# SHIFT_REGISTER_IC_74595.net
KiCad netlist of a schematic drawn in EAGLE
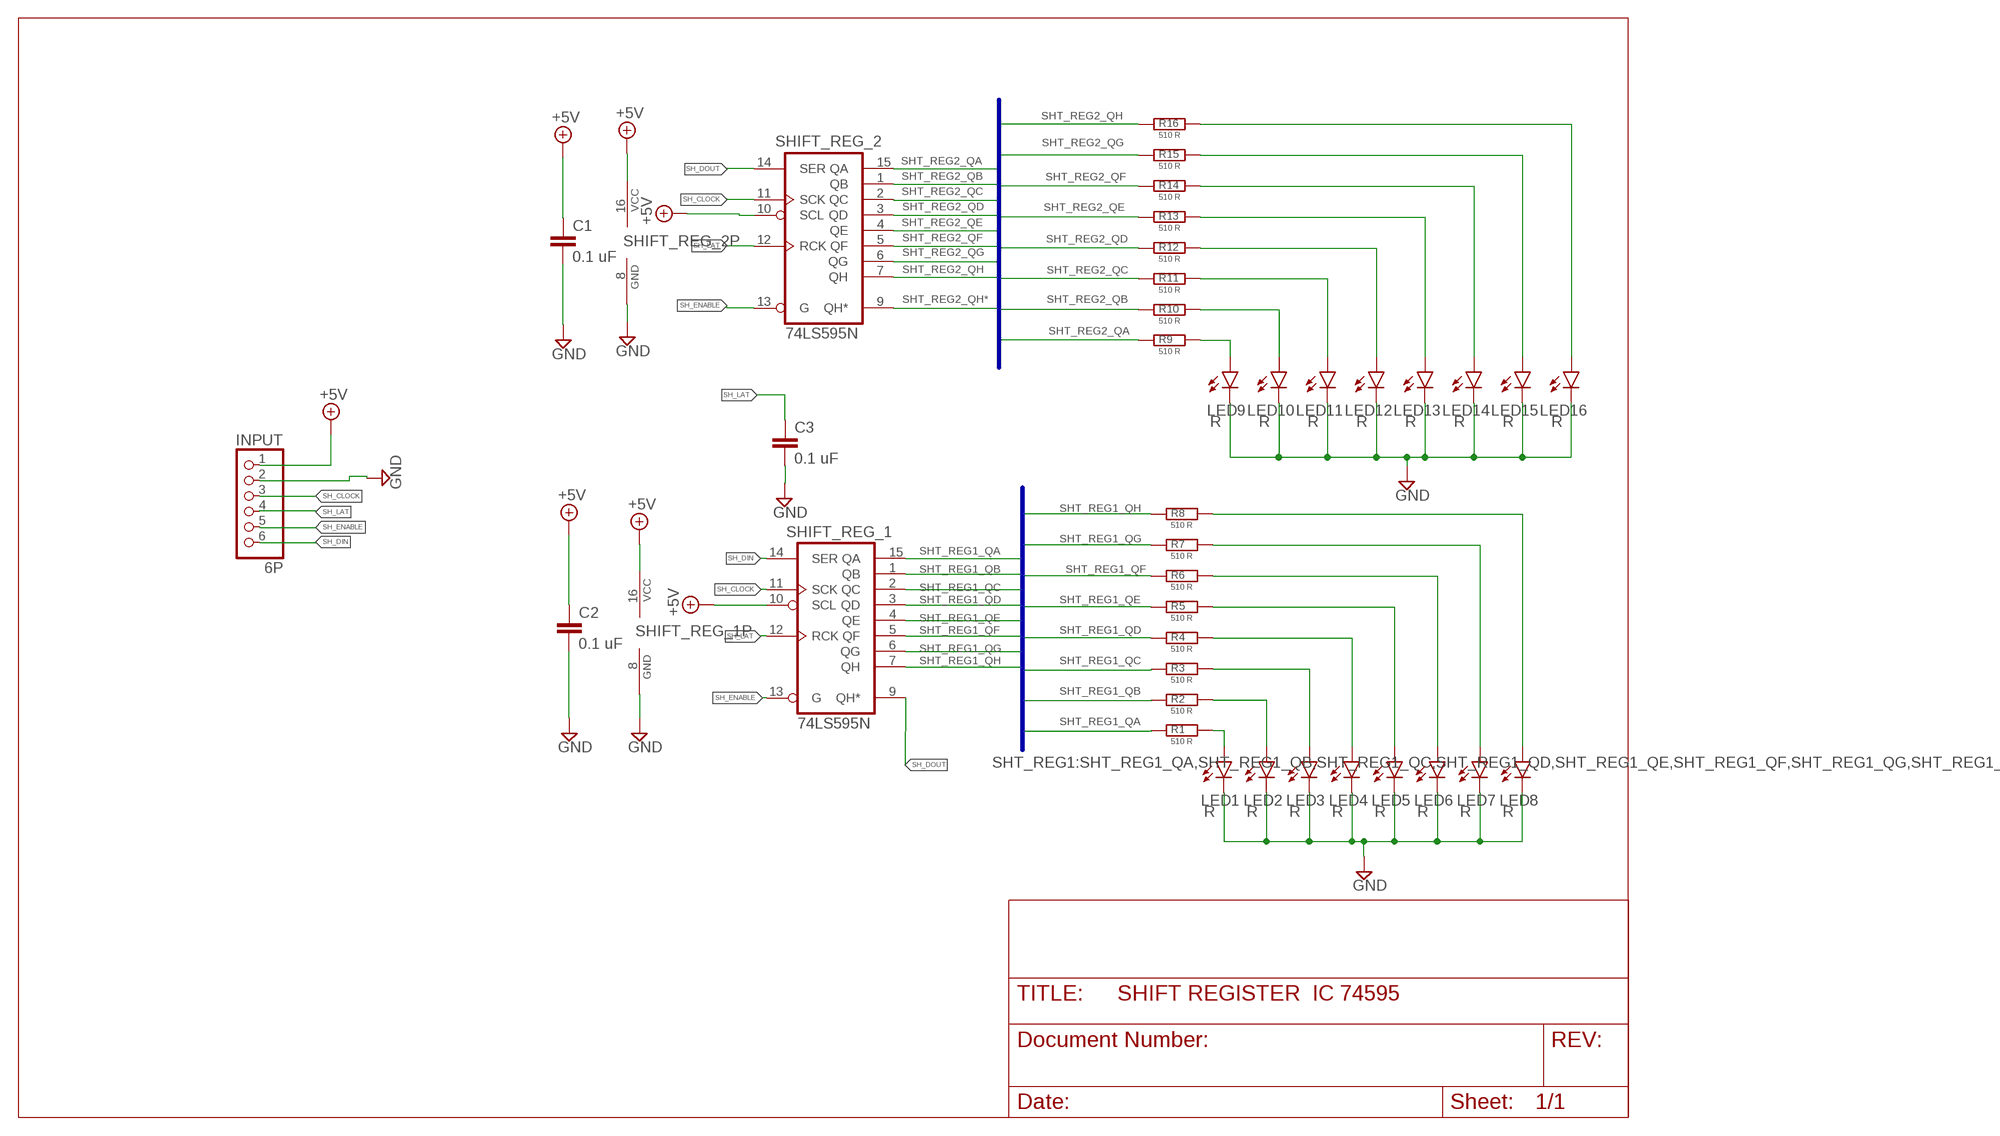
[diagram p0: schematic, sheet 1]

(export (version "E")
  (design (tool "Eeschema 10.0.6"))
  (components
    (comp (ref "C1")
      (value "0.1 uF")
      (footprint "eagle-import:C050-030X075")
      (libsource (lib "eagle-import") (part "C-EU050-030X075"))
    )
    (comp (ref "C2")
      (value "0.1 uF")
      (footprint "eagle-import:C050-030X075")
      (libsource (lib "eagle-import") (part "C-EU050-030X075"))
    )
    (comp (ref "C3")
      (value "0.1 uF")
      (footprint "eagle-import:C050-030X075")
      (libsource (lib "eagle-import") (part "C-EU050-030X075"))
    )
    (comp (ref "INPUT")
      (value "6P")
      (footprint "eagle-import:1X06_90")
      (libsource (lib "eagle-import") (part "PINHD-1X6/90"))
    )
    (comp (ref "LED1")
      (value "R")
      (footprint "eagle-import:LED5MM")
      (libsource (lib "eagle-import") (part "LED5MM"))
    )
    (comp (ref "LED2")
      (value "R")
      (footprint "eagle-import:LED5MM")
      (libsource (lib "eagle-import") (part "LED5MM"))
    )
    (comp (ref "LED3")
      (value "R")
      (footprint "eagle-import:LED5MM")
      (libsource (lib "eagle-import") (part "LED5MM"))
    )
    (comp (ref "LED4")
      (value "R")
      (footprint "eagle-import:LED5MM")
      (libsource (lib "eagle-import") (part "LED5MM"))
    )
    (comp (ref "LED5")
      (value "R")
      (footprint "eagle-import:LED5MM")
      (libsource (lib "eagle-import") (part "LED5MM"))
    )
    (comp (ref "LED6")
      (value "R")
      (footprint "eagle-import:LED5MM")
      (libsource (lib "eagle-import") (part "LED5MM"))
    )
    (comp (ref "LED7")
      (value "R")
      (footprint "eagle-import:LED5MM")
      (libsource (lib "eagle-import") (part "LED5MM"))
    )
    (comp (ref "LED8")
      (value "R")
      (footprint "eagle-import:LED5MM")
      (libsource (lib "eagle-import") (part "LED5MM"))
    )
    (comp (ref "LED9")
      (value "R")
      (footprint "eagle-import:LED5MM")
      (libsource (lib "eagle-import") (part "LED5MM"))
    )
    (comp (ref "LED10")
      (value "R")
      (footprint "eagle-import:LED5MM")
      (libsource (lib "eagle-import") (part "LED5MM"))
    )
    (comp (ref "LED11")
      (value "R")
      (footprint "eagle-import:LED5MM")
      (libsource (lib "eagle-import") (part "LED5MM"))
    )
    (comp (ref "LED12")
      (value "R")
      (footprint "eagle-import:LED5MM")
      (libsource (lib "eagle-import") (part "LED5MM"))
    )
    (comp (ref "LED13")
      (value "R")
      (footprint "eagle-import:LED5MM")
      (libsource (lib "eagle-import") (part "LED5MM"))
    )
    (comp (ref "LED14")
      (value "R")
      (footprint "eagle-import:LED5MM")
      (libsource (lib "eagle-import") (part "LED5MM"))
    )
    (comp (ref "LED15")
      (value "R")
      (footprint "eagle-import:LED5MM")
      (libsource (lib "eagle-import") (part "LED5MM"))
    )
    (comp (ref "LED16")
      (value "R")
      (footprint "eagle-import:LED5MM")
      (libsource (lib "eagle-import") (part "LED5MM"))
    )
    (comp (ref "R1")
      (value "510 R")
      (footprint "eagle-import:0207_10")
      (libsource (lib "eagle-import") (part "R-EU_0207/10"))
    )
    (comp (ref "R2")
      (value "510 R")
      (footprint "eagle-import:0207_10")
      (libsource (lib "eagle-import") (part "R-EU_0207/10"))
    )
    (comp (ref "R3")
      (value "510 R")
      (footprint "eagle-import:0207_10")
      (libsource (lib "eagle-import") (part "R-EU_0207/10"))
    )
    (comp (ref "R4")
      (value "510 R")
      (footprint "eagle-import:0207_10")
      (libsource (lib "eagle-import") (part "R-EU_0207/10"))
    )
    (comp (ref "R5")
      (value "510 R")
      (footprint "eagle-import:0207_10")
      (libsource (lib "eagle-import") (part "R-EU_0207/10"))
    )
    (comp (ref "R6")
      (value "510 R")
      (footprint "eagle-import:0207_10")
      (libsource (lib "eagle-import") (part "R-EU_0207/10"))
    )
    (comp (ref "R7")
      (value "510 R")
      (footprint "eagle-import:0207_10")
      (libsource (lib "eagle-import") (part "R-EU_0207/10"))
    )
    (comp (ref "R8")
      (value "510 R")
      (footprint "eagle-import:0207_10")
      (libsource (lib "eagle-import") (part "R-EU_0207/10"))
    )
    (comp (ref "R9")
      (value "510 R")
      (footprint "eagle-import:0207_10")
      (libsource (lib "eagle-import") (part "R-EU_0207/10"))
    )
    (comp (ref "R10")
      (value "510 R")
      (footprint "eagle-import:0207_10")
      (libsource (lib "eagle-import") (part "R-EU_0207/10"))
    )
    (comp (ref "R11")
      (value "510 R")
      (footprint "eagle-import:0207_10")
      (libsource (lib "eagle-import") (part "R-EU_0207/10"))
    )
    (comp (ref "R12")
      (value "510 R")
      (footprint "eagle-import:0207_10")
      (libsource (lib "eagle-import") (part "R-EU_0207/10"))
    )
    (comp (ref "R13")
      (value "510 R")
      (footprint "eagle-import:0207_10")
      (libsource (lib "eagle-import") (part "R-EU_0207/10"))
    )
    (comp (ref "R14")
      (value "510 R")
      (footprint "eagle-import:0207_10")
      (libsource (lib "eagle-import") (part "R-EU_0207/10"))
    )
    (comp (ref "R15")
      (value "510 R")
      (footprint "eagle-import:0207_10")
      (libsource (lib "eagle-import") (part "R-EU_0207/10"))
    )
    (comp (ref "R16")
      (value "510 R")
      (footprint "eagle-import:0207_10")
      (libsource (lib "eagle-import") (part "R-EU_0207/10"))
    )
    (comp (ref "SHIFT_REG_1")
      (value "74LS595N")
      (footprint "eagle-import:DIL16")
      (libsource (lib "eagle-import") (part "74595NLS"))
    )
    (comp (ref "SHIFT_REG_2")
      (value "74LS595N")
      (footprint "eagle-import:DIL16")
      (libsource (lib "eagle-import") (part "74595NLS"))
    )
  )
  (nets
    (net (code "3") (name "+5V") (class "Default")
      (node (ref "C1") (pin "1") (pinfunction "1_1") (pintype "passive"))
      (node (ref "C2") (pin "1") (pinfunction "1_1") (pintype "passive"))
      (node (ref "INPUT") (pin "1") (pinfunction "1_1") (pintype "passive"))
      (node (ref "SHIFT_REG_1") (pin "10") (pinfunction "SCL_10") (pintype "input"))
      (node (ref "SHIFT_REG_1") (pin "16") (pinfunction "VCC_16") (pintype "power_in"))
      (node (ref "SHIFT_REG_2") (pin "10") (pinfunction "SCL_10") (pintype "input"))
      (node (ref "SHIFT_REG_2") (pin "16") (pinfunction "VCC_16") (pintype "power_in"))
    )
    (net (code "4") (name "/SHT_REG1_QA") (class "Default")
      (node (ref "R1") (pin "1") (pinfunction "1_1") (pintype "passive"))
      (node (ref "SHIFT_REG_1") (pin "15") (pinfunction "QA_15") (pintype "tri_state"))
    )
    (net (code "5") (name "/SHT_REG1_QB") (class "Default")
      (node (ref "R2") (pin "1") (pinfunction "1_1") (pintype "passive"))
      (node (ref "SHIFT_REG_1") (pin "1") (pinfunction "QB_1") (pintype "tri_state"))
    )
    (net (code "6") (name "/SHT_REG1_QC") (class "Default")
      (node (ref "R3") (pin "1") (pinfunction "1_1") (pintype "passive"))
      (node (ref "SHIFT_REG_1") (pin "2") (pinfunction "QC_2") (pintype "tri_state"))
    )
    (net (code "7") (name "/SHT_REG1_QD") (class "Default")
      (node (ref "R4") (pin "1") (pinfunction "1_1") (pintype "passive"))
      (node (ref "SHIFT_REG_1") (pin "3") (pinfunction "QD_3") (pintype "tri_state"))
    )
    (net (code "8") (name "/SHT_REG1_QE") (class "Default")
      (node (ref "R5") (pin "1") (pinfunction "1_1") (pintype "passive"))
      (node (ref "SHIFT_REG_1") (pin "4") (pinfunction "QE_4") (pintype "tri_state"))
    )
    (net (code "9") (name "/SHT_REG1_QF") (class "Default")
      (node (ref "R6") (pin "1") (pinfunction "1_1") (pintype "passive"))
      (node (ref "SHIFT_REG_1") (pin "5") (pinfunction "QF_5") (pintype "tri_state"))
    )
    (net (code "10") (name "/SHT_REG1_QG") (class "Default")
      (node (ref "R7") (pin "1") (pinfunction "1_1") (pintype "passive"))
      (node (ref "SHIFT_REG_1") (pin "6") (pinfunction "QG_6") (pintype "tri_state"))
    )
    (net (code "11") (name "/SHT_REG1_QH") (class "Default")
      (node (ref "R8") (pin "1") (pinfunction "1_1") (pintype "passive"))
      (node (ref "SHIFT_REG_1") (pin "7") (pinfunction "QH_7") (pintype "tri_state"))
    )
    (net (code "12") (name "/SHT_REG2_QA") (class "Default")
      (node (ref "R9") (pin "1") (pinfunction "1_1") (pintype "passive"))
      (node (ref "SHIFT_REG_2") (pin "15") (pinfunction "QA_15") (pintype "tri_state"))
    )
    (net (code "13") (name "/SHT_REG2_QB") (class "Default")
      (node (ref "R10") (pin "1") (pinfunction "1_1") (pintype "passive"))
      (node (ref "SHIFT_REG_2") (pin "1") (pinfunction "QB_1") (pintype "tri_state"))
    )
    (net (code "14") (name "/SHT_REG2_QC") (class "Default")
      (node (ref "R11") (pin "1") (pinfunction "1_1") (pintype "passive"))
      (node (ref "SHIFT_REG_2") (pin "2") (pinfunction "QC_2") (pintype "tri_state"))
    )
    (net (code "15") (name "/SHT_REG2_QD") (class "Default")
      (node (ref "R12") (pin "1") (pinfunction "1_1") (pintype "passive"))
      (node (ref "SHIFT_REG_2") (pin "3") (pinfunction "QD_3") (pintype "tri_state"))
    )
    (net (code "16") (name "/SHT_REG2_QE") (class "Default")
      (node (ref "R13") (pin "1") (pinfunction "1_1") (pintype "passive"))
      (node (ref "SHIFT_REG_2") (pin "4") (pinfunction "QE_4") (pintype "tri_state"))
    )
    (net (code "17") (name "/SHT_REG2_QF") (class "Default")
      (node (ref "R14") (pin "1") (pinfunction "1_1") (pintype "passive"))
      (node (ref "SHIFT_REG_2") (pin "5") (pinfunction "QF_5") (pintype "tri_state"))
    )
    (net (code "18") (name "/SHT_REG2_QG") (class "Default")
      (node (ref "R15") (pin "1") (pinfunction "1_1") (pintype "passive"))
      (node (ref "SHIFT_REG_2") (pin "6") (pinfunction "QG_6") (pintype "tri_state"))
    )
    (net (code "19") (name "/SHT_REG2_QH") (class "Default")
      (node (ref "R16") (pin "1") (pinfunction "1_1") (pintype "passive"))
      (node (ref "SHIFT_REG_2") (pin "7") (pinfunction "QH_7") (pintype "tri_state"))
    )
    (net (code "20") (name "/SHT_REG2_QH*") (class "Default")
      (node (ref "SHIFT_REG_2") (pin "9") (pinfunction "QH*_9") (pintype "tri_state"))
    )
    (net (code "22") (name "GND") (class "Default")
      (node (ref "C1") (pin "2") (pinfunction "2_2") (pintype "passive"))
      (node (ref "C2") (pin "2") (pinfunction "2_2") (pintype "passive"))
      (node (ref "C3") (pin "2") (pinfunction "2_2") (pintype "passive"))
      (node (ref "INPUT") (pin "2") (pinfunction "2_2") (pintype "passive"))
      (node (ref "LED1") (pin "K") (pinfunction "C_K") (pintype "passive"))
      (node (ref "LED10") (pin "K") (pinfunction "C_K") (pintype "passive"))
      (node (ref "LED11") (pin "K") (pinfunction "C_K") (pintype "passive"))
      (node (ref "LED12") (pin "K") (pinfunction "C_K") (pintype "passive"))
      (node (ref "LED13") (pin "K") (pinfunction "C_K") (pintype "passive"))
      (node (ref "LED14") (pin "K") (pinfunction "C_K") (pintype "passive"))
      (node (ref "LED15") (pin "K") (pinfunction "C_K") (pintype "passive"))
      (node (ref "LED16") (pin "K") (pinfunction "C_K") (pintype "passive"))
      (node (ref "LED2") (pin "K") (pinfunction "C_K") (pintype "passive"))
      (node (ref "LED3") (pin "K") (pinfunction "C_K") (pintype "passive"))
      (node (ref "LED4") (pin "K") (pinfunction "C_K") (pintype "passive"))
      (node (ref "LED5") (pin "K") (pinfunction "C_K") (pintype "passive"))
      (node (ref "LED6") (pin "K") (pinfunction "C_K") (pintype "passive"))
      (node (ref "LED7") (pin "K") (pinfunction "C_K") (pintype "passive"))
      (node (ref "LED8") (pin "K") (pinfunction "C_K") (pintype "passive"))
      (node (ref "LED9") (pin "K") (pinfunction "C_K") (pintype "passive"))
      (node (ref "SHIFT_REG_1") (pin "8") (pinfunction "GND_8") (pintype "power_in"))
      (node (ref "SHIFT_REG_2") (pin "8") (pinfunction "GND_8") (pintype "power_in"))
    )
    (net (code "23") (name "Net-(LED1-PadA)") (class "Default")
      (node (ref "LED1") (pin "A") (pinfunction "A_A") (pintype "passive"))
      (node (ref "R1") (pin "2") (pinfunction "2_2") (pintype "passive"))
    )
    (net (code "24") (name "Net-(LED2-PadA)") (class "Default")
      (node (ref "LED2") (pin "A") (pinfunction "A_A") (pintype "passive"))
      (node (ref "R2") (pin "2") (pinfunction "2_2") (pintype "passive"))
    )
    (net (code "25") (name "Net-(LED3-PadA)") (class "Default")
      (node (ref "LED3") (pin "A") (pinfunction "A_A") (pintype "passive"))
      (node (ref "R3") (pin "2") (pinfunction "2_2") (pintype "passive"))
    )
    (net (code "26") (name "Net-(LED4-PadA)") (class "Default")
      (node (ref "LED4") (pin "A") (pinfunction "A_A") (pintype "passive"))
      (node (ref "R4") (pin "2") (pinfunction "2_2") (pintype "passive"))
    )
    (net (code "27") (name "Net-(LED5-PadA)") (class "Default")
      (node (ref "LED5") (pin "A") (pinfunction "A_A") (pintype "passive"))
      (node (ref "R5") (pin "2") (pinfunction "2_2") (pintype "passive"))
    )
    (net (code "28") (name "Net-(LED6-PadA)") (class "Default")
      (node (ref "LED6") (pin "A") (pinfunction "A_A") (pintype "passive"))
      (node (ref "R6") (pin "2") (pinfunction "2_2") (pintype "passive"))
    )
    (net (code "29") (name "Net-(LED7-PadA)") (class "Default")
      (node (ref "LED7") (pin "A") (pinfunction "A_A") (pintype "passive"))
      (node (ref "R7") (pin "2") (pinfunction "2_2") (pintype "passive"))
    )
    (net (code "30") (name "Net-(LED8-PadA)") (class "Default")
      (node (ref "LED8") (pin "A") (pinfunction "A_A") (pintype "passive"))
      (node (ref "R8") (pin "2") (pinfunction "2_2") (pintype "passive"))
    )
    (net (code "31") (name "Net-(LED9-PadA)") (class "Default")
      (node (ref "LED9") (pin "A") (pinfunction "A_A") (pintype "passive"))
      (node (ref "R9") (pin "2") (pinfunction "2_2") (pintype "passive"))
    )
    (net (code "32") (name "Net-(LED10-PadA)") (class "Default")
      (node (ref "LED10") (pin "A") (pinfunction "A_A") (pintype "passive"))
      (node (ref "R10") (pin "2") (pinfunction "2_2") (pintype "passive"))
    )
    (net (code "33") (name "Net-(LED11-PadA)") (class "Default")
      (node (ref "LED11") (pin "A") (pinfunction "A_A") (pintype "passive"))
      (node (ref "R11") (pin "2") (pinfunction "2_2") (pintype "passive"))
    )
    (net (code "34") (name "Net-(LED12-PadA)") (class "Default")
      (node (ref "LED12") (pin "A") (pinfunction "A_A") (pintype "passive"))
      (node (ref "R12") (pin "2") (pinfunction "2_2") (pintype "passive"))
    )
    (net (code "35") (name "Net-(LED13-PadA)") (class "Default")
      (node (ref "LED13") (pin "A") (pinfunction "A_A") (pintype "passive"))
      (node (ref "R13") (pin "2") (pinfunction "2_2") (pintype "passive"))
    )
    (net (code "36") (name "Net-(LED14-PadA)") (class "Default")
      (node (ref "LED14") (pin "A") (pinfunction "A_A") (pintype "passive"))
      (node (ref "R14") (pin "2") (pinfunction "2_2") (pintype "passive"))
    )
    (net (code "37") (name "Net-(LED15-PadA)") (class "Default")
      (node (ref "LED15") (pin "A") (pinfunction "A_A") (pintype "passive"))
      (node (ref "R15") (pin "2") (pinfunction "2_2") (pintype "passive"))
    )
    (net (code "38") (name "Net-(LED16-PadA)") (class "Default")
      (node (ref "LED16") (pin "A") (pinfunction "A_A") (pintype "passive"))
      (node (ref "R16") (pin "2") (pinfunction "2_2") (pintype "passive"))
    )
    (net (code "39") (name "SH_CLOCK") (class "Default")
      (node (ref "INPUT") (pin "3") (pinfunction "3_3") (pintype "passive"))
      (node (ref "SHIFT_REG_1") (pin "11") (pinfunction "SCK_11") (pintype "input"))
      (node (ref "SHIFT_REG_2") (pin "11") (pinfunction "SCK_11") (pintype "input"))
    )
    (net (code "40") (name "SH_DIN") (class "Default")
      (node (ref "INPUT") (pin "6") (pinfunction "6_6") (pintype "passive"))
      (node (ref "SHIFT_REG_1") (pin "14") (pinfunction "SER_14") (pintype "input"))
    )
    (net (code "41") (name "SH_DOUT") (class "Default")
      (node (ref "SHIFT_REG_1") (pin "9") (pinfunction "QH*_9") (pintype "tri_state"))
      (node (ref "SHIFT_REG_2") (pin "14") (pinfunction "SER_14") (pintype "input"))
    )
    (net (code "42") (name "SH_ENABLE") (class "Default")
      (node (ref "INPUT") (pin "5") (pinfunction "5_5") (pintype "passive"))
      (node (ref "SHIFT_REG_1") (pin "13") (pinfunction "G_13") (pintype "input"))
      (node (ref "SHIFT_REG_2") (pin "13") (pinfunction "G_13") (pintype "input"))
    )
    (net (code "43") (name "SH_LAT") (class "Default")
      (node (ref "C3") (pin "1") (pinfunction "1_1") (pintype "passive"))
      (node (ref "INPUT") (pin "4") (pinfunction "4_4") (pintype "passive"))
      (node (ref "SHIFT_REG_1") (pin "12") (pinfunction "RCK_12") (pintype "input"))
      (node (ref "SHIFT_REG_2") (pin "12") (pinfunction "RCK_12") (pintype "input"))
    )
  )
)
